# ESP32.net
KiCad netlist of a schematic drawn in Altium Designer
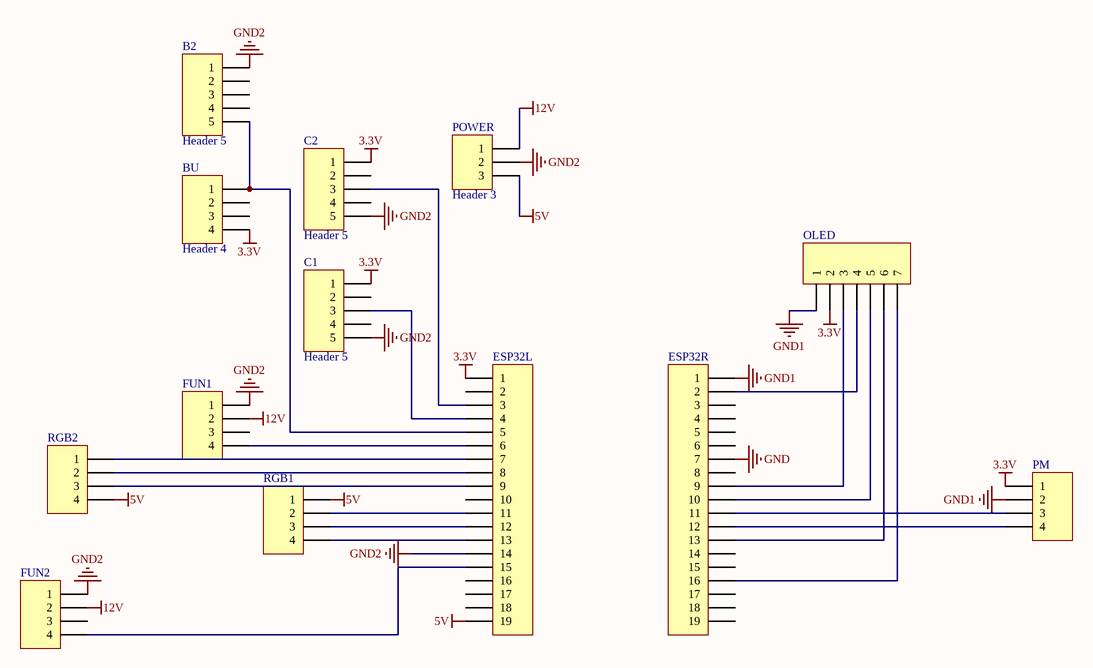
[diagram p0: ESP32.SchDoc]

(export (version "E")
  (design (tool "Eeschema 10.0.6"))
  (components
    (comp (ref "B2")
      (value "Header 5")
      (footprint "HDR1X5")
      (description "Header, 5-Pin")
      (fields (field (name "PUBLISHER") "Altium Limited"))
      (libsource (lib "Miscellaneous Connectors") (part "Header 5"))
    )
    (comp (ref "BU")
      (value "Header 4")
      (footprint "HDR1X4")
      (description "Header, 4-Pin")
      (fields (field (name "PUBLISHER") "Altium Limited"))
      (libsource (lib "Miscellaneous Connectors") (part "Header 4"))
    )
    (comp (ref "C1")
      (value "Header 5")
      (footprint "HDR1X5")
      (description "Header, 5-Pin")
      (fields (field (name "PUBLISHER") "Altium Limited"))
      (libsource (lib "Miscellaneous Connectors") (part "Header 5"))
    )
    (comp (ref "C2")
      (value "Header 5")
      (footprint "HDR1X5")
      (description "Header, 5-Pin")
      (fields (field (name "PUBLISHER") "Altium Limited"))
      (libsource (lib "Miscellaneous Connectors") (part "Header 5"))
    )
    (comp (ref "ESP32L")
      (value "Header 19")
      (footprint "HDR1X19")
      (description "Header, 19-Pin")
      (fields (field (name "PUBLISHER") "Altium Limited"))
      (libsource (lib "Miscellaneous Connectors") (part "Header 19"))
    )
    (comp (ref "ESP32R")
      (value "Header 19")
      (footprint "HDR1X19")
      (description "Header, 19-Pin")
      (fields (field (name "PUBLISHER") "Altium Limited"))
      (libsource (lib "") (part "Header 19_1"))
    )
    (comp (ref "FUN1")
      (value "Header 4")
      (footprint "HDR1X4")
      (description "Header, 4-Pin")
      (fields (field (name "PUBLISHER") "Altium Limited"))
      (libsource (lib "Miscellaneous Connectors") (part "Header 4"))
    )
    (comp (ref "FUN2")
      (value "Header 4")
      (footprint "HDR1X4")
      (description "Header, 4-Pin")
      (fields (field (name "PUBLISHER") "Altium Limited"))
      (libsource (lib "Miscellaneous Connectors") (part "Header 4"))
    )
    (comp (ref "OLED")
      (value "Header 7")
      (footprint "HDR1X7")
      (description "Header, 7-Pin")
      (fields (field (name "PUBLISHER") "Altium Limited"))
      (libsource (lib "Miscellaneous Connectors") (part "Header 7"))
    )
    (comp (ref "PM")
      (value "Header 4")
      (footprint "HDR1X4")
      (description "Header, 4-Pin")
      (fields (field (name "PUBLISHER") "Altium Limited"))
      (libsource (lib "") (part "Header 4_1"))
    )
    (comp (ref "POWER")
      (value "Header 3")
      (footprint "HDR1X3")
      (description "Header, 3-Pin")
      (fields (field (name "PUBLISHER") "Altium Limited"))
      (libsource (lib "Miscellaneous Connectors") (part "Header 3"))
    )
    (comp (ref "RGB1")
      (value "Header 4")
      (footprint "HDR1X4")
      (description "Header, 4-Pin")
      (fields (field (name "PUBLISHER") "Altium Limited"))
      (libsource (lib "Miscellaneous Connectors") (part "Header 4"))
    )
    (comp (ref "RGB2")
      (value "Header 4")
      (footprint "HDR1X4")
      (description "Header, 4-Pin")
      (fields (field (name "PUBLISHER") "Altium Limited"))
      (libsource (lib "Miscellaneous Connectors") (part "Header 4"))
    )
  )
  (nets
    (net (code "1") (name "3.3V") (class "Default")
      (node (ref "BU") (pin "4") (pinfunction "4_4") (pintype "passive"))
      (node (ref "C1") (pin "1") (pinfunction "1_1") (pintype "passive"))
      (node (ref "C2") (pin "1") (pinfunction "1_1") (pintype "passive"))
      (node (ref "ESP32L") (pin "1") (pinfunction "1_1") (pintype "passive"))
      (node (ref "OLED") (pin "2") (pinfunction "2_2") (pintype "passive"))
      (node (ref "PM") (pin "1") (pinfunction "1_1") (pintype "passive"))
    )
    (net (code "2") (name "5V") (class "Default")
      (node (ref "ESP32L") (pin "19") (pinfunction "19_19") (pintype "passive"))
      (node (ref "POWER") (pin "3") (pinfunction "3_3") (pintype "passive"))
      (node (ref "RGB1") (pin "1") (pinfunction "1_1") (pintype "passive"))
      (node (ref "RGB2") (pin "4") (pinfunction "4_4") (pintype "passive"))
    )
    (net (code "3") (name "12V") (class "Default")
      (node (ref "FUN1") (pin "2") (pinfunction "2_2") (pintype "passive"))
      (node (ref "FUN2") (pin "2") (pinfunction "2_2") (pintype "passive"))
      (node (ref "POWER") (pin "1") (pinfunction "1_1") (pintype "passive"))
    )
    (net (code "4") (name "GND") (class "Default")
      (node (ref "ESP32R") (pin "7") (pinfunction "7_7") (pintype "passive"))
    )
    (net (code "5") (name "GND1") (class "Default")
      (node (ref "ESP32R") (pin "1") (pinfunction "1_1") (pintype "passive"))
      (node (ref "OLED") (pin "1") (pinfunction "1_1") (pintype "passive"))
      (node (ref "PM") (pin "2") (pinfunction "2_2") (pintype "passive"))
    )
    (net (code "6") (name "GND2") (class "Default")
      (node (ref "B2") (pin "1") (pinfunction "1_1") (pintype "passive"))
      (node (ref "C1") (pin "5") (pinfunction "5_5") (pintype "passive"))
      (node (ref "C2") (pin "5") (pinfunction "5_5") (pintype "passive"))
      (node (ref "ESP32L") (pin "14") (pinfunction "14_14") (pintype "passive"))
      (node (ref "FUN1") (pin "1") (pinfunction "1_1") (pintype "passive"))
      (node (ref "FUN2") (pin "1") (pinfunction "1_1") (pintype "passive"))
      (node (ref "POWER") (pin "2") (pinfunction "2_2") (pintype "passive"))
    )
    (net (code "7") (name "Net-(B2-Pad5)") (class "Default")
      (node (ref "B2") (pin "5") (pinfunction "5_5") (pintype "passive"))
      (node (ref "BU") (pin "1") (pinfunction "1_1") (pintype "passive"))
      (node (ref "ESP32L") (pin "5") (pinfunction "5_5") (pintype "passive"))
    )
    (net (code "8") (name "Net-(C1-Pad3)") (class "Default")
      (node (ref "C1") (pin "3") (pinfunction "3_3") (pintype "passive"))
      (node (ref "ESP32L") (pin "4") (pinfunction "4_4") (pintype "passive"))
    )
    (net (code "9") (name "Net-(C2-Pad3)") (class "Default")
      (node (ref "C2") (pin "3") (pinfunction "3_3") (pintype "passive"))
      (node (ref "ESP32L") (pin "3") (pinfunction "3_3") (pintype "passive"))
    )
    (net (code "10") (name "Net-(ESP32L-Pad6)") (class "Default")
      (node (ref "ESP32L") (pin "6") (pinfunction "6_6") (pintype "passive"))
      (node (ref "FUN1") (pin "4") (pinfunction "4_4") (pintype "passive"))
    )
    (net (code "11") (name "Net-(ESP32L-Pad7)") (class "Default")
      (node (ref "ESP32L") (pin "7") (pinfunction "7_7") (pintype "passive"))
      (node (ref "RGB2") (pin "1") (pinfunction "1_1") (pintype "passive"))
    )
    (net (code "12") (name "Net-(ESP32L-Pad8)") (class "Default")
      (node (ref "ESP32L") (pin "8") (pinfunction "8_8") (pintype "passive"))
      (node (ref "RGB2") (pin "2") (pinfunction "2_2") (pintype "passive"))
    )
    (net (code "13") (name "Net-(ESP32L-Pad9)") (class "Default")
      (node (ref "ESP32L") (pin "9") (pinfunction "9_9") (pintype "passive"))
      (node (ref "RGB2") (pin "3") (pinfunction "3_3") (pintype "passive"))
    )
    (net (code "14") (name "Net-(ESP32L-Pad11)") (class "Default")
      (node (ref "ESP32L") (pin "11") (pinfunction "11_11") (pintype "passive"))
      (node (ref "RGB1") (pin "2") (pinfunction "2_2") (pintype "passive"))
    )
    (net (code "15") (name "Net-(ESP32L-Pad12)") (class "Default")
      (node (ref "ESP32L") (pin "12") (pinfunction "12_12") (pintype "passive"))
      (node (ref "RGB1") (pin "3") (pinfunction "3_3") (pintype "passive"))
    )
    (net (code "16") (name "Net-(ESP32L-Pad13)") (class "Default")
      (node (ref "ESP32L") (pin "13") (pinfunction "13_13") (pintype "passive"))
      (node (ref "RGB1") (pin "4") (pinfunction "4_4") (pintype "passive"))
    )
    (net (code "17") (name "Net-(ESP32L-Pad15)") (class "Default")
      (node (ref "ESP32L") (pin "15") (pinfunction "15_15") (pintype "passive"))
      (node (ref "FUN2") (pin "4") (pinfunction "4_4") (pintype "passive"))
    )
    (net (code "18") (name "Net-(ESP32R-Pad2)") (class "Default")
      (node (ref "ESP32R") (pin "2") (pinfunction "2_2") (pintype "passive"))
      (node (ref "OLED") (pin "4") (pinfunction "4_4") (pintype "passive"))
    )
    (net (code "19") (name "Net-(ESP32R-Pad9)") (class "Default")
      (node (ref "ESP32R") (pin "9") (pinfunction "9_9") (pintype "passive"))
      (node (ref "OLED") (pin "3") (pinfunction "3_3") (pintype "passive"))
    )
    (net (code "20") (name "Net-(ESP32R-Pad10)") (class "Default")
      (node (ref "ESP32R") (pin "10") (pinfunction "10_10") (pintype "passive"))
      (node (ref "OLED") (pin "5") (pinfunction "5_5") (pintype "passive"))
    )
    (net (code "21") (name "Net-(ESP32R-Pad11)") (class "Default")
      (node (ref "ESP32R") (pin "11") (pinfunction "11_11") (pintype "passive"))
      (node (ref "PM") (pin "3") (pinfunction "3_3") (pintype "passive"))
    )
    (net (code "22") (name "Net-(ESP32R-Pad12)") (class "Default")
      (node (ref "ESP32R") (pin "12") (pinfunction "12_12") (pintype "passive"))
      (node (ref "PM") (pin "4") (pinfunction "4_4") (pintype "passive"))
    )
    (net (code "23") (name "Net-(ESP32R-Pad13)") (class "Default")
      (node (ref "ESP32R") (pin "13") (pinfunction "13_13") (pintype "passive"))
      (node (ref "OLED") (pin "6") (pinfunction "6_6") (pintype "passive"))
    )
    (net (code "24") (name "Net-(ESP32R-Pad16)") (class "Default")
      (node (ref "ESP32R") (pin "16") (pinfunction "16_16") (pintype "passive"))
      (node (ref "OLED") (pin "7") (pinfunction "7_7") (pintype "passive"))
    )
    (net (code "25") (name "unconnected-(B2-Pad2)") (class "Default")
      (node (ref "B2") (pin "2") (pinfunction "2_2") (pintype "passive"))
    )
    (net (code "26") (name "unconnected-(B2-Pad3)") (class "Default")
      (node (ref "B2") (pin "3") (pinfunction "3_3") (pintype "passive"))
    )
    (net (code "27") (name "unconnected-(B2-Pad4)") (class "Default")
      (node (ref "B2") (pin "4") (pinfunction "4_4") (pintype "passive"))
    )
    (net (code "28") (name "unconnected-(BU-Pad2)") (class "Default")
      (node (ref "BU") (pin "2") (pinfunction "2_2") (pintype "passive"))
    )
    (net (code "29") (name "unconnected-(BU-Pad3)") (class "Default")
      (node (ref "BU") (pin "3") (pinfunction "3_3") (pintype "passive"))
    )
    (net (code "30") (name "unconnected-(C1-Pad2)") (class "Default")
      (node (ref "C1") (pin "2") (pinfunction "2_2") (pintype "passive"))
    )
    (net (code "31") (name "unconnected-(C1-Pad4)") (class "Default")
      (node (ref "C1") (pin "4") (pinfunction "4_4") (pintype "passive"))
    )
    (net (code "32") (name "unconnected-(C2-Pad2)") (class "Default")
      (node (ref "C2") (pin "2") (pinfunction "2_2") (pintype "passive"))
    )
    (net (code "33") (name "unconnected-(C2-Pad4)") (class "Default")
      (node (ref "C2") (pin "4") (pinfunction "4_4") (pintype "passive"))
    )
    (net (code "34") (name "unconnected-(ESP32L-Pad2)") (class "Default")
      (node (ref "ESP32L") (pin "2") (pinfunction "2_2") (pintype "passive"))
    )
    (net (code "35") (name "unconnected-(ESP32L-Pad10)") (class "Default")
      (node (ref "ESP32L") (pin "10") (pinfunction "10_10") (pintype "passive"))
    )
    (net (code "36") (name "unconnected-(ESP32L-Pad16)") (class "Default")
      (node (ref "ESP32L") (pin "16") (pinfunction "16_16") (pintype "passive"))
    )
    (net (code "37") (name "unconnected-(ESP32L-Pad17)") (class "Default")
      (node (ref "ESP32L") (pin "17") (pinfunction "17_17") (pintype "passive"))
    )
    (net (code "38") (name "unconnected-(ESP32L-Pad18)") (class "Default")
      (node (ref "ESP32L") (pin "18") (pinfunction "18_18") (pintype "passive"))
    )
    (net (code "39") (name "unconnected-(ESP32R-Pad3)") (class "Default")
      (node (ref "ESP32R") (pin "3") (pinfunction "3_3") (pintype "passive"))
    )
    (net (code "40") (name "unconnected-(ESP32R-Pad4)") (class "Default")
      (node (ref "ESP32R") (pin "4") (pinfunction "4_4") (pintype "passive"))
    )
    (net (code "41") (name "unconnected-(ESP32R-Pad5)") (class "Default")
      (node (ref "ESP32R") (pin "5") (pinfunction "5_5") (pintype "passive"))
    )
    (net (code "42") (name "unconnected-(ESP32R-Pad6)") (class "Default")
      (node (ref "ESP32R") (pin "6") (pinfunction "6_6") (pintype "passive"))
    )
    (net (code "43") (name "unconnected-(ESP32R-Pad8)") (class "Default")
      (node (ref "ESP32R") (pin "8") (pinfunction "8_8") (pintype "passive"))
    )
    (net (code "44") (name "unconnected-(ESP32R-Pad14)") (class "Default")
      (node (ref "ESP32R") (pin "14") (pinfunction "14_14") (pintype "passive"))
    )
    (net (code "45") (name "unconnected-(ESP32R-Pad15)") (class "Default")
      (node (ref "ESP32R") (pin "15") (pinfunction "15_15") (pintype "passive"))
    )
    (net (code "46") (name "unconnected-(ESP32R-Pad17)") (class "Default")
      (node (ref "ESP32R") (pin "17") (pinfunction "17_17") (pintype "passive"))
    )
    (net (code "47") (name "unconnected-(ESP32R-Pad18)") (class "Default")
      (node (ref "ESP32R") (pin "18") (pinfunction "18_18") (pintype "passive"))
    )
    (net (code "48") (name "unconnected-(ESP32R-Pad19)") (class "Default")
      (node (ref "ESP32R") (pin "19") (pinfunction "19_19") (pintype "passive"))
    )
    (net (code "49") (name "unconnected-(FUN1-Pad3)") (class "Default")
      (node (ref "FUN1") (pin "3") (pinfunction "3_3") (pintype "passive"))
    )
    (net (code "50") (name "unconnected-(FUN2-Pad3)") (class "Default")
      (node (ref "FUN2") (pin "3") (pinfunction "3_3") (pintype "passive"))
    )
  )
)
